# ADXL377_Breakout-v1_01.net
KiCad netlist of a schematic drawn in EAGLE
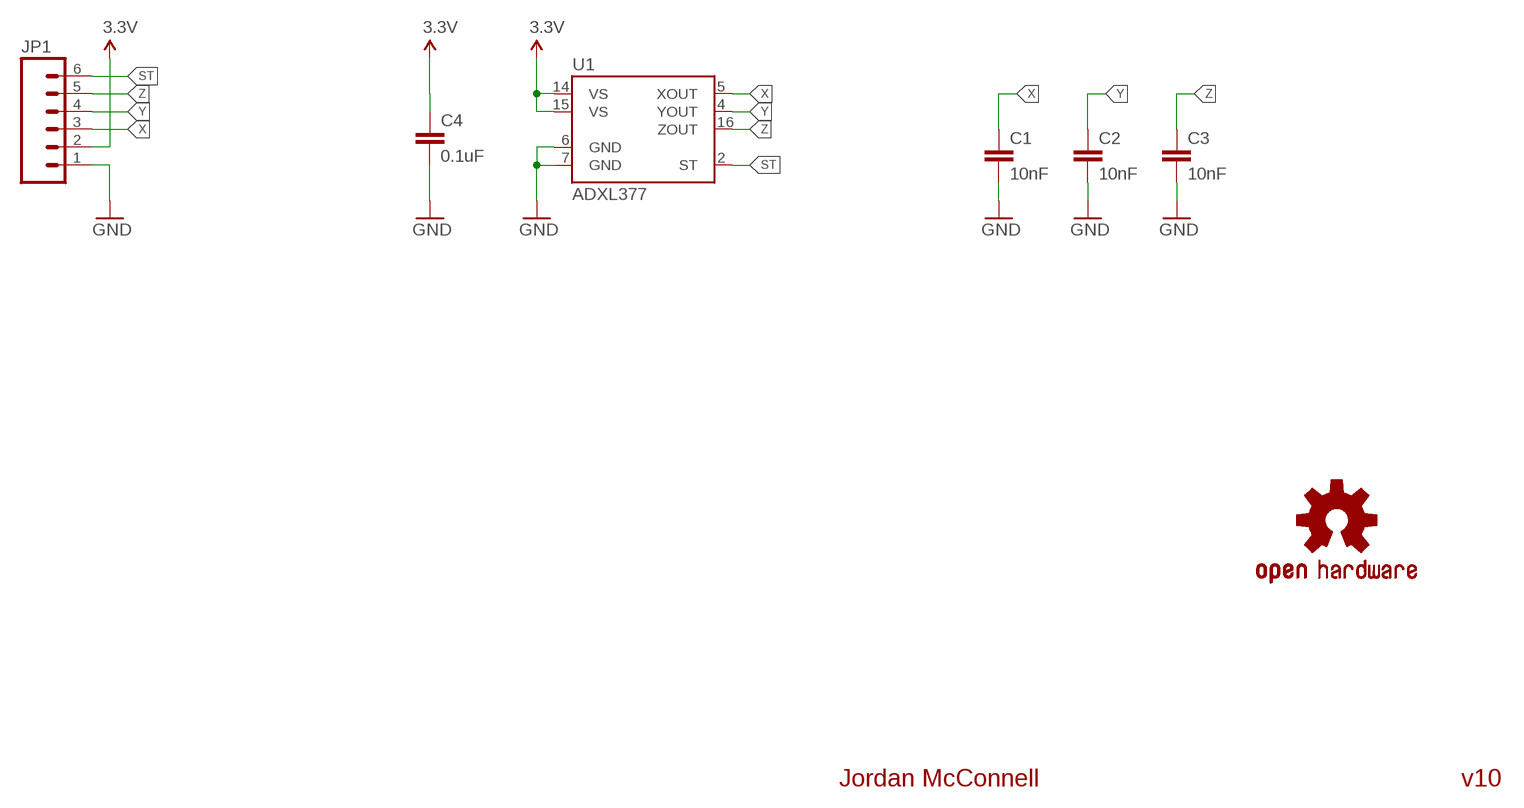
[diagram p0: schematic, sheet 1]

(export (version "E")
  (design (tool "Eeschema 10.0.6"))
  (components
    (comp (ref "C1")
      (value "10nF")
      (footprint "eagle-import:0603-CAP")
      (libsource (lib "eagle-import") (part "10NF/10000PF-50V-10%(0603)"))
    )
    (comp (ref "C2")
      (value "10nF")
      (footprint "eagle-import:0603-CAP")
      (libsource (lib "eagle-import") (part "10NF/10000PF-50V-10%(0603)"))
    )
    (comp (ref "C3")
      (value "10nF")
      (footprint "eagle-import:0603-CAP")
      (libsource (lib "eagle-import") (part "10NF/10000PF-50V-10%(0603)"))
    )
    (comp (ref "C4")
      (value "0.1uF")
      (footprint "eagle-import:0603-CAP")
      (libsource (lib "eagle-import") (part "0.1UF-25V(+80/-20%)(0603)"))
    )
    (comp (ref "JP1")
      (value "M06SIP")
      (footprint "eagle-import:1X06")
      (libsource (lib "eagle-import") (part "M06SIP"))
    )
    (comp (ref "LOGO2")
      (value "OSHW-LOGOS")
      (footprint "eagle-import:OSHW-LOGO-S")
      (libsource (lib "eagle-import") (part "OSHW-LOGOS"))
    )
    (comp (ref "U1")
      (value "ADXL377")
      (footprint "eagle-import:LFCSP_LQ-16")
      (libsource (lib "eagle-import") (part "ADXL377"))
    )
  )
  (nets
    (net (code "1") (name "3.3V") (class "Default")
      (node (ref "C4") (pin "1") (pinfunction "1_1") (pintype "passive"))
      (node (ref "JP1") (pin "2") (pinfunction "2_2") (pintype "passive"))
      (node (ref "U1") (pin "14") (pinfunction "VS_14") (pintype "bidirectional"))
      (node (ref "U1") (pin "15") (pinfunction "VS_15") (pintype "bidirectional"))
    )
    (net (code "2") (name "GND") (class "Default")
      (node (ref "C1") (pin "2") (pinfunction "2_2") (pintype "passive"))
      (node (ref "C2") (pin "2") (pinfunction "2_2") (pintype "passive"))
      (node (ref "C3") (pin "2") (pinfunction "2_2") (pintype "passive"))
      (node (ref "C4") (pin "2") (pinfunction "2_2") (pintype "passive"))
      (node (ref "JP1") (pin "1") (pinfunction "1_1") (pintype "passive"))
      (node (ref "U1") (pin "6") (pinfunction "GND_6") (pintype "bidirectional"))
      (node (ref "U1") (pin "7") (pinfunction "GND_7") (pintype "bidirectional"))
    )
    (net (code "3") (name "ST") (class "Default")
      (node (ref "JP1") (pin "6") (pinfunction "6_6") (pintype "passive"))
      (node (ref "U1") (pin "2") (pinfunction "ST_2") (pintype "bidirectional"))
    )
    (net (code "4") (name "X") (class "Default")
      (node (ref "C1") (pin "1") (pinfunction "1_1") (pintype "passive"))
      (node (ref "JP1") (pin "3") (pinfunction "3_3") (pintype "passive"))
      (node (ref "U1") (pin "5") (pinfunction "XOUT_5") (pintype "bidirectional"))
    )
    (net (code "5") (name "Y") (class "Default")
      (node (ref "C2") (pin "1") (pinfunction "1_1") (pintype "passive"))
      (node (ref "JP1") (pin "4") (pinfunction "4_4") (pintype "passive"))
      (node (ref "U1") (pin "4") (pinfunction "YOUT_4") (pintype "bidirectional"))
    )
    (net (code "6") (name "Z") (class "Default")
      (node (ref "C3") (pin "1") (pinfunction "1_1") (pintype "passive"))
      (node (ref "JP1") (pin "5") (pinfunction "5_5") (pintype "passive"))
      (node (ref "U1") (pin "16") (pinfunction "ZOUT_16") (pintype "bidirectional"))
    )
  )
)
